# schematic.net
KiCad netlist of a schematic drawn in Altium Designer
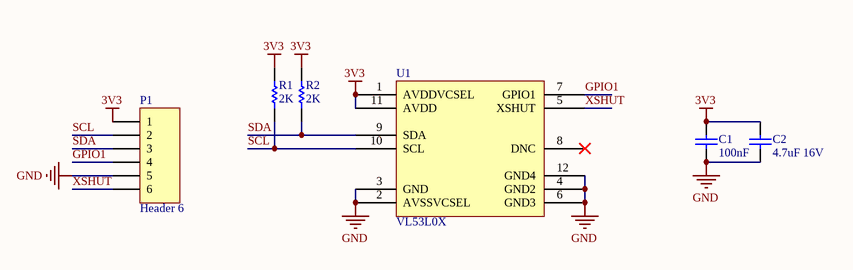
[diagram p0: schematic.SchDoc]

(export (version "E")
  (design (tool "Eeschema 10.0.6"))
  (components
    (comp (ref "C1")
      (value "100nF")
      (footprint "0603 Cap")
      (description "CAP CER 0.1UF 16V X7R 0603")
      (fields
        (field (name "MANUFACTURER") "KEMET")
        (field (name "MANUFACTURER PART NUMBER") "C0603C104K4RACTU")
      )
      (libsource (lib "Componentes_base") (part "C0603C104K4RACTU"))
    )
    (comp (ref "C2")
      (value "4.7uF 16V")
      (footprint "0805 CAP")
      (description "CAP CER 4.7UF 16V X7R 0805")
      (fields
        (field (name "MANUFACTURER") "Murata Electronics North America")
        (field (name "MANUFACTURER PART NUMBER") "GRM21BR71C475KE51L")
      )
      (libsource (lib "Componentes_base") (part "GRM21BR71C475KE51L"))
    )
    (comp (ref "P1")
      (value "Header 6")
      (footprint "HDR1X6")
      (description "Header, 6-Pin")
      (fields (field (name "PUBLISHER") "Altium Limited"))
      (libsource (lib "Miscellaneous Connectors") (part "Header 6"))
    )
    (comp (ref "R1")
      (value "2K")
      (footprint "0603 Res")
      (description "RES SMD 2K OHM 1% 1/10W 0603")
      (fields
        (field (name "MANUFACTURER") "Yageo")
        (field (name "MANUFACTURER PART NUMBER") "RC0603FR-072KL")
      )
      (libsource (lib "Componentes_base") (part "RC0603FR-072KL"))
    )
    (comp (ref "R2")
      (value "2K")
      (footprint "0603 Res")
      (description "RES SMD 2K OHM 1% 1/10W 0603")
      (fields
        (field (name "MANUFACTURER") "Yageo")
        (field (name "MANUFACTURER PART NUMBER") "RC0603FR-072KL")
      )
      (libsource (lib "Componentes_base") (part "RC0603FR-072KL"))
    )
    (comp (ref "U1")
      (value "VL53L0X")
      (description "TOF distance sensor")
      (libsource (lib "Componentes_base") (part "VL53L0X"))
    )
  )
  (nets
    (net (code "1") (name "/GPIO1") (class "Default")
      (node (ref "P1") (pin "4") (pinfunction "4_4") (pintype "passive"))
      (node (ref "U1") (pin "7") (pinfunction "GPIO1_7") (pintype "passive"))
    )
    (net (code "2") (name "/SCL") (class "Default")
      (node (ref "P1") (pin "2") (pinfunction "2_2") (pintype "passive"))
      (node (ref "R1") (pin "1") (pinfunction "1_1") (pintype "passive"))
      (node (ref "U1") (pin "10") (pinfunction "SCL_10") (pintype "passive"))
    )
    (net (code "3") (name "/SDA") (class "Default")
      (node (ref "P1") (pin "3") (pinfunction "3_3") (pintype "passive"))
      (node (ref "R2") (pin "1") (pinfunction "1_1") (pintype "passive"))
      (node (ref "U1") (pin "9") (pinfunction "SDA_9") (pintype "passive"))
    )
    (net (code "4") (name "/XSHUT") (class "Default")
      (node (ref "P1") (pin "6") (pinfunction "6_6") (pintype "passive"))
      (node (ref "U1") (pin "5") (pinfunction "XSHUT_5") (pintype "passive"))
    )
    (net (code "5") (name "3V3") (class "Default")
      (node (ref "C1") (pin "2") (pinfunction "2_2") (pintype "passive"))
      (node (ref "C2") (pin "2") (pinfunction "2_2") (pintype "passive"))
      (node (ref "P1") (pin "1") (pinfunction "1_1") (pintype "passive"))
      (node (ref "R1") (pin "2") (pinfunction "2_2") (pintype "passive"))
      (node (ref "R2") (pin "2") (pinfunction "2_2") (pintype "passive"))
      (node (ref "U1") (pin "1") (pinfunction "AVDDVCSEL_1") (pintype "passive"))
      (node (ref "U1") (pin "11") (pinfunction "AVDD_11") (pintype "passive"))
    )
    (net (code "6") (name "GND") (class "Default")
      (node (ref "C1") (pin "1") (pinfunction "1_1") (pintype "passive"))
      (node (ref "C2") (pin "1") (pinfunction "1_1") (pintype "passive"))
      (node (ref "P1") (pin "5") (pinfunction "5_5") (pintype "passive"))
      (node (ref "U1") (pin "12") (pinfunction "GND4_12") (pintype "passive"))
      (node (ref "U1") (pin "2") (pinfunction "AVSSVCSEL_2") (pintype "passive"))
      (node (ref "U1") (pin "3") (pinfunction "GND_3") (pintype "passive"))
      (node (ref "U1") (pin "4") (pinfunction "GND2_4") (pintype "passive"))
      (node (ref "U1") (pin "6") (pinfunction "GND3_6") (pintype "passive"))
    )
    (net (code "7") (name "unconnected-(U1-DNC-Pad8)") (class "Default")
      (node (ref "U1") (pin "8") (pinfunction "DNC_8") (pintype "passive+no_connect"))
    )
  )
)
